# Modulo_Led_RGB.net
KiCad netlist of a schematic drawn in Altium Designer
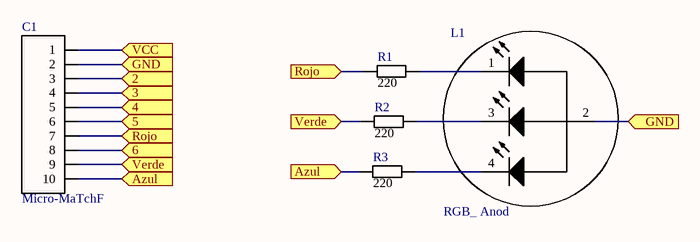
[diagram p0: Modulo_Led_RGB.SchDoc]

(export (version "E")
  (design (tool "Eeschema 10.0.6"))
  (components
    (comp (ref "C1")
      (value "Micro-MaTchF")
      (footprint "Micro-MaTch Famale 1.27mm/SMD")
      (description "Micro-MaTch Famale 1.27mm T/Hole")
      (libsource (lib "Libreria_Borxo_Sch") (part "Micro-MaTchF"))
    )
    (comp (ref "L1")
      (value "RGB_ Anod")
      (footprint "Led 5mm - RGB")
      (description "Typical BLUE SiC LED")
      (libsource (lib "Libreria_Borxo_Sch") (part "RGB_ Anod"))
    )
    (comp (ref "R1")
      (value "220")
      (footprint "1206 (3216)")
      (description "Resistor")
      (fields (field (name "Comment") "Res") (field (name "AUTOR") "Borxo García"))
      (libsource (lib "Libreria_Borxo_Sch") (part "Res2"))
    )
    (comp (ref "R2")
      (value "220")
      (footprint "1206 (3216)")
      (description "Resistor")
      (fields (field (name "Comment") "Res") (field (name "AUTOR") "Borxo García"))
      (libsource (lib "Libreria_Borxo_Sch") (part "Res2"))
    )
    (comp (ref "R3")
      (value "220")
      (footprint "1206 (3216)")
      (description "Resistor")
      (fields (field (name "Comment") "Res") (field (name "AUTOR") "Borxo García"))
      (libsource (lib "Libreria_Borxo_Sch") (part "Res2"))
    )
  )
  (nets
    (net (code "1") (name "/2") (class "Default")
      (node (ref "C1") (pin "3") (pinfunction "3_3") (pintype "passive"))
    )
    (net (code "2") (name "/3") (class "Default")
      (node (ref "C1") (pin "4") (pinfunction "4_4") (pintype "passive"))
    )
    (net (code "3") (name "/4") (class "Default")
      (node (ref "C1") (pin "5") (pinfunction "5_5") (pintype "passive"))
    )
    (net (code "4") (name "/5") (class "Default")
      (node (ref "C1") (pin "6") (pinfunction "6_6") (pintype "passive"))
    )
    (net (code "5") (name "/6") (class "Default")
      (node (ref "C1") (pin "8") (pinfunction "8_8") (pintype "passive"))
    )
    (net (code "6") (name "/Azul") (class "Default")
      (node (ref "C1") (pin "10") (pinfunction "10_10") (pintype "passive"))
      (node (ref "R3") (pin "1") (pinfunction "1_1") (pintype "passive"))
    )
    (net (code "7") (name "/GND") (class "Default")
      (node (ref "C1") (pin "2") (pinfunction "2_2") (pintype "passive"))
      (node (ref "L1") (pin "2") (pinfunction "K_2") (pintype "passive"))
    )
    (net (code "8") (name "/Rojo") (class "Default")
      (node (ref "C1") (pin "7") (pinfunction "7_7") (pintype "passive"))
      (node (ref "R1") (pin "1") (pinfunction "1_1") (pintype "passive"))
    )
    (net (code "9") (name "/VCC") (class "Default")
      (node (ref "C1") (pin "1") (pinfunction "1_1") (pintype "passive"))
    )
    (net (code "10") (name "/Verde") (class "Default")
      (node (ref "C1") (pin "9") (pinfunction "9_9") (pintype "passive"))
      (node (ref "R2") (pin "1") (pinfunction "1_1") (pintype "passive"))
    )
    (net (code "11") (name "Net-(L1-A-Pad1)") (class "Default")
      (node (ref "L1") (pin "1") (pinfunction "A_1") (pintype "passive"))
      (node (ref "R1") (pin "2") (pinfunction "2_2") (pintype "passive"))
    )
    (net (code "12") (name "Net-(L1-A-Pad3)") (class "Default")
      (node (ref "L1") (pin "3") (pinfunction "A_3") (pintype "passive"))
      (node (ref "R2") (pin "2") (pinfunction "2_2") (pintype "passive"))
    )
    (net (code "13") (name "Net-(L1-A-Pad4)") (class "Default")
      (node (ref "L1") (pin "4") (pinfunction "A_4") (pintype "passive"))
      (node (ref "R3") (pin "2") (pinfunction "2_2") (pintype "passive"))
    )
  )
)
